# MODUL_STEP_V100.net
KiCad netlist of a schematic drawn in EAGLE
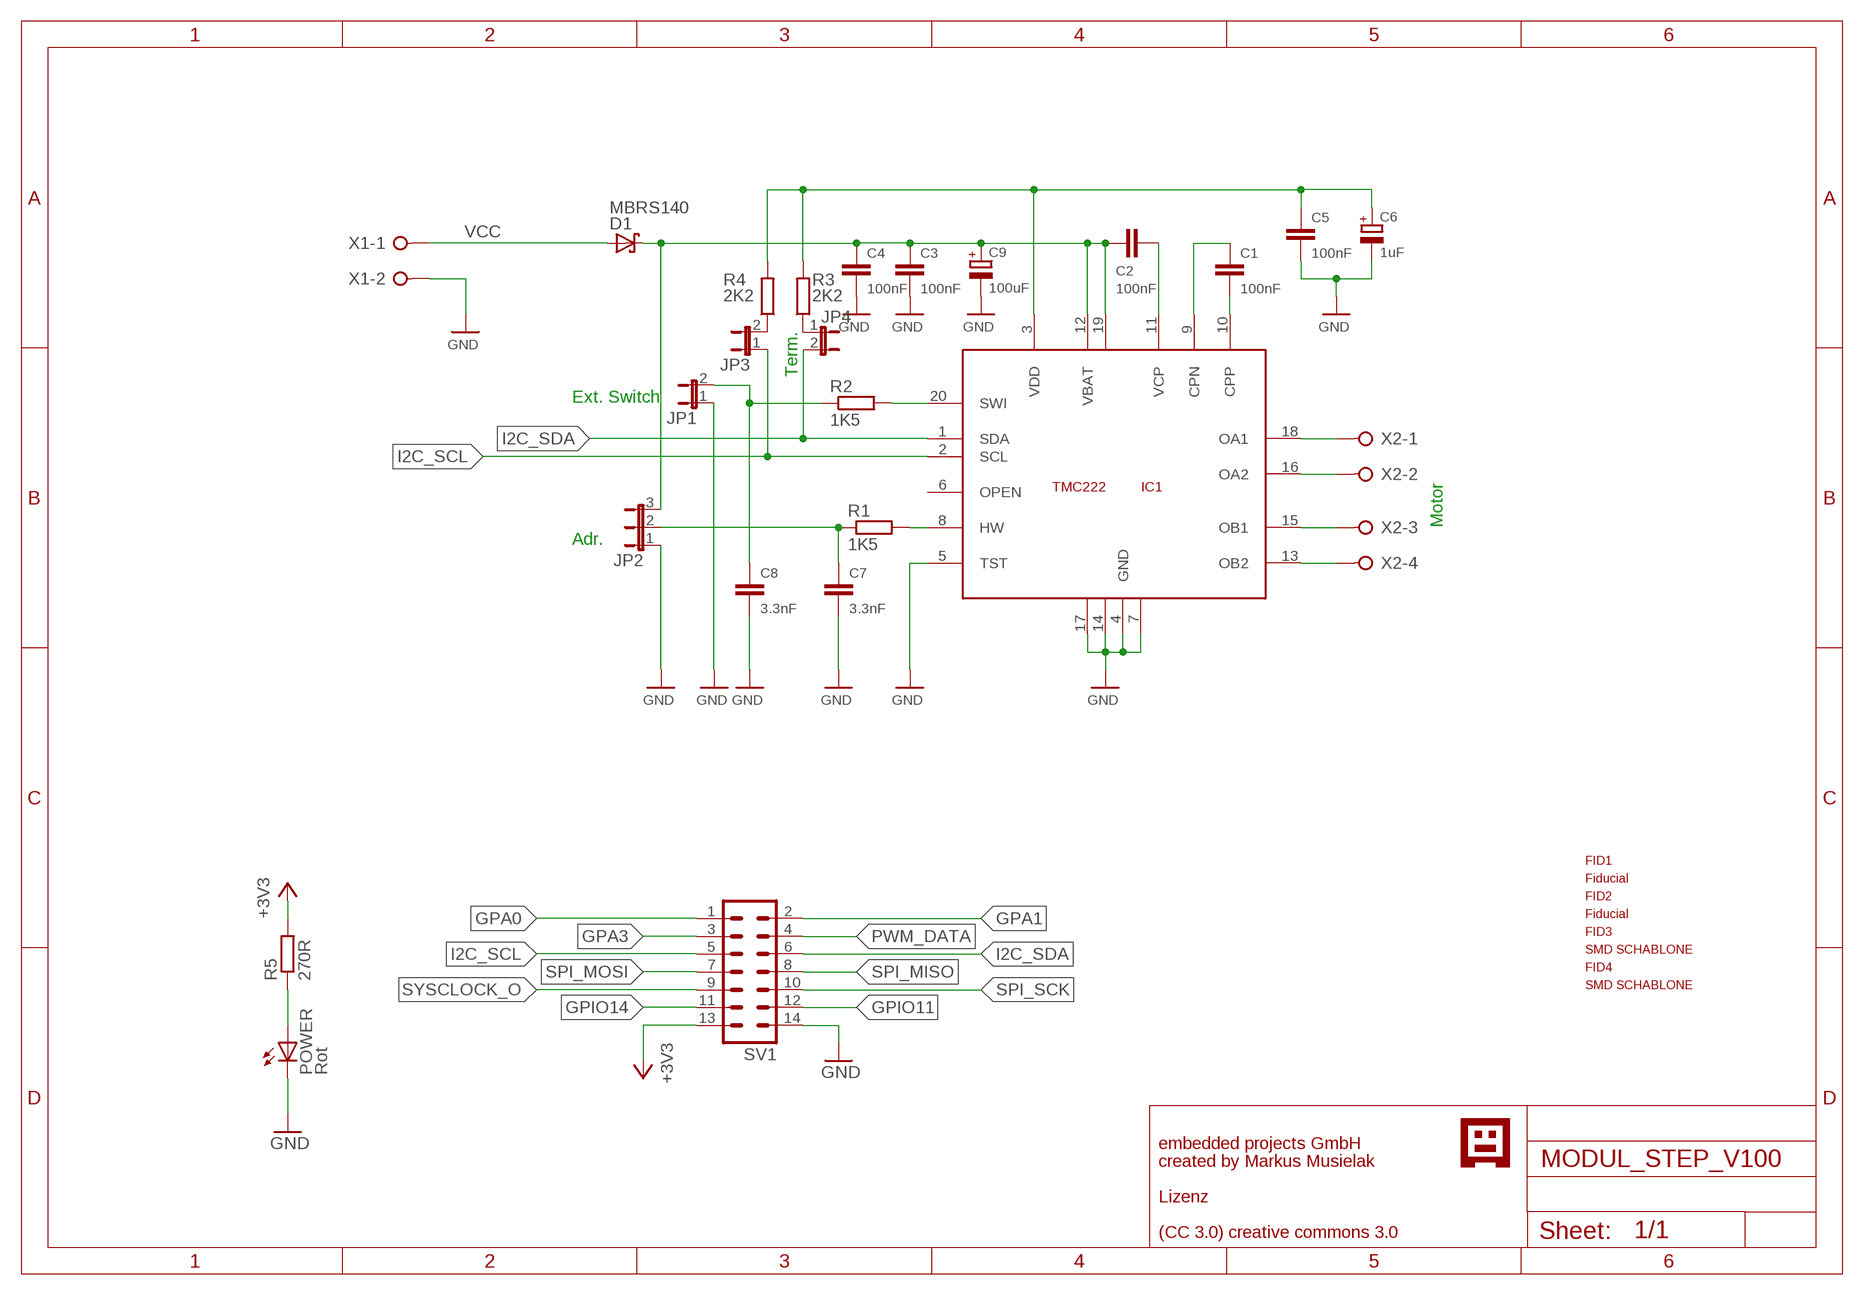
[diagram p0: schematic, sheet 1]

(export (version "E")
  (design (tool "Eeschema 10.0.6"))
  (components
    (comp (ref "C1")
      (value "100nF")
      (footprint "eagle-import:C0805")
      (libsource (lib "eagle-import") (part "C-EUC0805"))
    )
    (comp (ref "C2")
      (value "100nF")
      (footprint "eagle-import:C0805")
      (libsource (lib "eagle-import") (part "C-EUC0805"))
    )
    (comp (ref "C3")
      (value "100nF")
      (footprint "eagle-import:C0805")
      (libsource (lib "eagle-import") (part "C-EUC0805"))
    )
    (comp (ref "C4")
      (value "100nF")
      (footprint "eagle-import:C0805")
      (libsource (lib "eagle-import") (part "C-EUC0805"))
    )
    (comp (ref "C5")
      (value "100nF")
      (footprint "eagle-import:C0805")
      (libsource (lib "eagle-import") (part "C-EUC0805"))
    )
    (comp (ref "C6")
      (value "1uF")
      (footprint "eagle-import:B_3528-21R")
      (libsource (lib "eagle-import") (part "CPOL-EUB/3528-21R"))
    )
    (comp (ref "C7")
      (value "3.3nF")
      (footprint "eagle-import:C0805")
      (libsource (lib "eagle-import") (part "C-EUC0805"))
    )
    (comp (ref "C8")
      (value "3.3nF")
      (footprint "eagle-import:C0805")
      (libsource (lib "eagle-import") (part "C-EUC0805"))
    )
    (comp (ref "C9")
      (value "100uF")
      (footprint "eagle-import:E5-10,5")
      (libsource (lib "eagle-import") (part "CPOL-EUE5-10.5"))
    )
    (comp (ref "D1")
      (value "MBRS140")
      (footprint "eagle-import:SMB")
      (libsource (lib "eagle-import") (part "SCHOTTKY-DIODESMD"))
    )
    (comp (ref "FID1")
      (value "PASSERMARKEN_FIDUCIAL")
      (footprint "eagle-import:PASSERMARKEN_FIDUCIAL")
      (libsource (lib "eagle-import") (part "PASSERMARKEN_FIDUCIAL"))
    )
    (comp (ref "FID2")
      (value "PASSERMARKEN_FIDUCIAL")
      (footprint "eagle-import:PASSERMARKEN_FIDUCIAL")
      (libsource (lib "eagle-import") (part "PASSERMARKEN_FIDUCIAL"))
    )
    (comp (ref "FID3")
      (value "PASSERMARKEN_FIDUCIAL")
      (footprint "eagle-import:PASSERMARKEN_FIDUCIAL")
      (libsource (lib "eagle-import") (part "SMDSCHABLONE_PASSERMARKEN_FIDUCIAL"))
    )
    (comp (ref "FID4")
      (value "PASSERMARKEN_FIDUCIAL")
      (footprint "eagle-import:PASSERMARKEN_FIDUCIAL")
      (libsource (lib "eagle-import") (part "SMDSCHABLONE_PASSERMARKEN_FIDUCIAL"))
    )
    (comp (ref "IC1")
      (value "TMC222")
      (footprint "eagle-import:SOIC20")
      (libsource (lib "eagle-import") (part "TMC222"))
    )
    (comp (ref "JP1")
      (value "JP1E")
      (footprint "eagle-import:JP1")
      (libsource (lib "eagle-import") (part "JP1E"))
    )
    (comp (ref "JP2")
      (value "JP2E")
      (footprint "eagle-import:JP2")
      (libsource (lib "eagle-import") (part "JP2E"))
    )
    (comp (ref "JP3")
      (value "JP1E")
      (footprint "eagle-import:JP1")
      (libsource (lib "eagle-import") (part "JP1E"))
    )
    (comp (ref "JP4")
      (value "JP1E")
      (footprint "eagle-import:JP1")
      (libsource (lib "eagle-import") (part "JP1E"))
    )
    (comp (ref "POWER")
      (value "Rot")
      (footprint "eagle-import:CHIP-LED0805")
      (libsource (lib "eagle-import") (part "LEDCHIP-LED0805"))
    )
    (comp (ref "R1")
      (value "1K5")
      (footprint "eagle-import:R0805")
      (libsource (lib "eagle-import") (part "R-EU_R0805"))
    )
    (comp (ref "R2")
      (value "1K5")
      (footprint "eagle-import:R0805")
      (libsource (lib "eagle-import") (part "R-EU_R0805"))
    )
    (comp (ref "R3")
      (value "2K2")
      (footprint "eagle-import:R0805")
      (libsource (lib "eagle-import") (part "R-EU_R0805"))
    )
    (comp (ref "R4")
      (value "2K2")
      (footprint "eagle-import:R0805")
      (libsource (lib "eagle-import") (part "R-EU_R0805"))
    )
    (comp (ref "R5")
      (value "270R")
      (footprint "eagle-import:R0805")
      (libsource (lib "eagle-import") (part "resistor_R-EU_R0805"))
    )
    (comp (ref "SV1")
      (value "ML14")
      (footprint "eagle-import:ML14")
      (libsource (lib "eagle-import") (part "ML14"))
    )
    (comp (ref "U$1")
      (value "GNUBLINLOGOSIEB")
      (footprint "eagle-import:GNUSIEBDRUCK")
      (libsource (lib "eagle-import") (part "GNUBLINLOGOSIEB"))
    )
    (comp (ref "X1")
      (value "W237-02P")
      (footprint "eagle-import:W237-132")
      (libsource (lib "eagle-import") (part "W237-02P"))
    )
    (comp (ref "X2")
      (value "W237-04P")
      (footprint "eagle-import:W237-4P")
      (libsource (lib "eagle-import") (part "W237-04P"))
    )
  )
  (nets
    (net (code "1") (name "+3V3") (class "Default")
      (node (ref "R5") (pin "2") (pinfunction "2_2") (pintype "passive"))
      (node (ref "SV1") (pin "13") (pinfunction "13_13") (pintype "passive"))
    )
    (net (code "2") (name "/VCC") (class "Default")
      (node (ref "D1") (pin "A") (pinfunction "A_A") (pintype "passive"))
      (node (ref "X1") (pin "1") (pinfunction "KL_1") (pintype "passive"))
    )
    (net (code "3") (name "GND") (class "Default")
      (node (ref "C3") (pin "2") (pinfunction "2_2") (pintype "passive"))
      (node (ref "C4") (pin "2") (pinfunction "2_2") (pintype "passive"))
      (node (ref "C5") (pin "2") (pinfunction "2_2") (pintype "passive"))
      (node (ref "C6") (pin "-") (pinfunction "-_-") (pintype "passive"))
      (node (ref "C7") (pin "2") (pinfunction "2_2") (pintype "passive"))
      (node (ref "C8") (pin "2") (pinfunction "2_2") (pintype "passive"))
      (node (ref "C9") (pin "-") (pinfunction "-_-") (pintype "passive"))
      (node (ref "IC1") (pin "14") (pinfunction "GND3_14") (pintype "bidirectional"))
      (node (ref "IC1") (pin "17") (pinfunction "GND4_17") (pintype "bidirectional"))
      (node (ref "IC1") (pin "4") (pinfunction "GND_4") (pintype "bidirectional"))
      (node (ref "IC1") (pin "5") (pinfunction "TST_5") (pintype "bidirectional"))
      (node (ref "IC1") (pin "7") (pinfunction "GND2_7") (pintype "bidirectional"))
      (node (ref "JP1") (pin "1") (pinfunction "1_1") (pintype "passive"))
      (node (ref "JP2") (pin "1") (pinfunction "1_1") (pintype "passive"))
      (node (ref "POWER") (pin "C") (pinfunction "C_C") (pintype "passive"))
      (node (ref "SV1") (pin "14") (pinfunction "14_14") (pintype "passive"))
      (node (ref "X1") (pin "2") (pinfunction "KL_2") (pintype "passive"))
    )
    (net (code "4") (name "GPA0") (class "Default")
      (node (ref "SV1") (pin "1") (pinfunction "1_1") (pintype "passive"))
    )
    (net (code "5") (name "GPA1") (class "Default")
      (node (ref "SV1") (pin "2") (pinfunction "2_2") (pintype "passive"))
    )
    (net (code "6") (name "GPA3") (class "Default")
      (node (ref "SV1") (pin "3") (pinfunction "3_3") (pintype "passive"))
    )
    (net (code "7") (name "GPIO11") (class "Default")
      (node (ref "SV1") (pin "12") (pinfunction "12_12") (pintype "passive"))
    )
    (net (code "8") (name "GPIO14") (class "Default")
      (node (ref "SV1") (pin "11") (pinfunction "11_11") (pintype "passive"))
    )
    (net (code "9") (name "I2C_SCL") (class "Default")
      (node (ref "IC1") (pin "2") (pinfunction "SCL_2") (pintype "bidirectional"))
      (node (ref "JP3") (pin "1") (pinfunction "1_1") (pintype "passive"))
      (node (ref "SV1") (pin "5") (pinfunction "5_5") (pintype "passive"))
    )
    (net (code "10") (name "I2C_SDA") (class "Default")
      (node (ref "IC1") (pin "1") (pinfunction "SDA_1") (pintype "bidirectional"))
      (node (ref "JP4") (pin "2") (pinfunction "2_2") (pintype "passive"))
      (node (ref "SV1") (pin "6") (pinfunction "6_6") (pintype "passive"))
    )
    (net (code "11") (name "Net-(C7-Pad1)") (class "Default")
      (node (ref "C7") (pin "1") (pinfunction "1_1") (pintype "passive"))
      (node (ref "JP2") (pin "2") (pinfunction "2_2") (pintype "passive"))
      (node (ref "R1") (pin "1") (pinfunction "1_1") (pintype "passive"))
    )
    (net (code "12") (name "Net-(C8-Pad1)") (class "Default")
      (node (ref "C8") (pin "1") (pinfunction "1_1") (pintype "passive"))
      (node (ref "JP1") (pin "2") (pinfunction "2_2") (pintype "passive"))
      (node (ref "R2") (pin "1") (pinfunction "1_1") (pintype "passive"))
    )
    (net (code "13") (name "Net-(IC1-CPN)") (class "Default")
      (node (ref "C1") (pin "1") (pinfunction "1_1") (pintype "passive"))
      (node (ref "IC1") (pin "9") (pinfunction "CPN_9") (pintype "bidirectional"))
    )
    (net (code "14") (name "Net-(IC1-CPP)") (class "Default")
      (node (ref "C1") (pin "2") (pinfunction "2_2") (pintype "passive"))
      (node (ref "IC1") (pin "10") (pinfunction "CPP_10") (pintype "bidirectional"))
    )
    (net (code "15") (name "Net-(IC1-HW)") (class "Default")
      (node (ref "IC1") (pin "8") (pinfunction "HW_8") (pintype "bidirectional"))
      (node (ref "R1") (pin "2") (pinfunction "2_2") (pintype "passive"))
    )
    (net (code "16") (name "Net-(IC1-OA1)") (class "Default")
      (node (ref "IC1") (pin "18") (pinfunction "OA1_18") (pintype "bidirectional"))
      (node (ref "X2") (pin "1") (pinfunction "KL_1") (pintype "passive"))
    )
    (net (code "17") (name "Net-(IC1-OA2)") (class "Default")
      (node (ref "IC1") (pin "16") (pinfunction "OA2_16") (pintype "bidirectional"))
      (node (ref "X2") (pin "2") (pinfunction "KL_2") (pintype "passive"))
    )
    (net (code "18") (name "Net-(IC1-OB1)") (class "Default")
      (node (ref "IC1") (pin "15") (pinfunction "OB1_15") (pintype "bidirectional"))
      (node (ref "X2") (pin "3") (pinfunction "KL_3") (pintype "passive"))
    )
    (net (code "19") (name "Net-(IC1-OB2)") (class "Default")
      (node (ref "IC1") (pin "13") (pinfunction "OB2_13") (pintype "bidirectional"))
      (node (ref "X2") (pin "4") (pinfunction "KL_4") (pintype "passive"))
    )
    (net (code "20") (name "Net-(IC1-SWI)") (class "Default")
      (node (ref "IC1") (pin "20") (pinfunction "SWI_20") (pintype "bidirectional"))
      (node (ref "R2") (pin "2") (pinfunction "2_2") (pintype "passive"))
    )
    (net (code "21") (name "Net-(IC1-VBAT)") (class "Default")
      (node (ref "C2") (pin "1") (pinfunction "1_1") (pintype "passive"))
      (node (ref "C3") (pin "1") (pinfunction "1_1") (pintype "passive"))
      (node (ref "C4") (pin "1") (pinfunction "1_1") (pintype "passive"))
      (node (ref "C9") (pin "+") (pinfunction "+_+") (pintype "passive"))
      (node (ref "D1") (pin "C") (pinfunction "C_C") (pintype "passive"))
      (node (ref "IC1") (pin "12") (pinfunction "VBAT_12") (pintype "bidirectional"))
      (node (ref "IC1") (pin "19") (pinfunction "VBAT2_19") (pintype "bidirectional"))
      (node (ref "JP2") (pin "3") (pinfunction "3_3") (pintype "passive"))
    )
    (net (code "22") (name "Net-(IC1-VCP)") (class "Default")
      (node (ref "C2") (pin "2") (pinfunction "2_2") (pintype "passive"))
      (node (ref "IC1") (pin "11") (pinfunction "VCP_11") (pintype "bidirectional"))
    )
    (net (code "23") (name "Net-(IC1-VDD)") (class "Default")
      (node (ref "C5") (pin "1") (pinfunction "1_1") (pintype "passive"))
      (node (ref "C6") (pin "+") (pinfunction "+_+") (pintype "passive"))
      (node (ref "IC1") (pin "3") (pinfunction "VDD_3") (pintype "bidirectional"))
      (node (ref "R3") (pin "2") (pinfunction "2_2") (pintype "passive"))
      (node (ref "R4") (pin "2") (pinfunction "2_2") (pintype "passive"))
    )
    (net (code "24") (name "Net-(JP3-Pad2)") (class "Default")
      (node (ref "JP3") (pin "2") (pinfunction "2_2") (pintype "passive"))
      (node (ref "R4") (pin "1") (pinfunction "1_1") (pintype "passive"))
    )
    (net (code "25") (name "Net-(JP4-Pad1)") (class "Default")
      (node (ref "JP4") (pin "1") (pinfunction "1_1") (pintype "passive"))
      (node (ref "R3") (pin "1") (pinfunction "1_1") (pintype "passive"))
    )
    (net (code "26") (name "Net-(POWER-PadA)") (class "Default")
      (node (ref "POWER") (pin "A") (pinfunction "A_A") (pintype "passive"))
      (node (ref "R5") (pin "1") (pinfunction "1_1") (pintype "passive"))
    )
    (net (code "27") (name "PWM_DATA") (class "Default")
      (node (ref "SV1") (pin "4") (pinfunction "4_4") (pintype "passive"))
    )
    (net (code "28") (name "SPI_MISO") (class "Default")
      (node (ref "SV1") (pin "8") (pinfunction "8_8") (pintype "passive"))
    )
    (net (code "29") (name "SPI_MOSI") (class "Default")
      (node (ref "SV1") (pin "7") (pinfunction "7_7") (pintype "passive"))
    )
    (net (code "30") (name "SPI_SCK") (class "Default")
      (node (ref "SV1") (pin "10") (pinfunction "10_10") (pintype "passive"))
    )
    (net (code "31") (name "SYSCLOCK_O") (class "Default")
      (node (ref "SV1") (pin "9") (pinfunction "9_9") (pintype "passive"))
    )
    (net (code "32") (name "unconnected-(IC1-OPEN-Pad6)") (class "Default")
      (node (ref "IC1") (pin "6") (pinfunction "OPEN_6") (pintype "bidirectional"))
    )
  )
)
